# daplink_pzh.net
KiCad netlist of a schematic drawn in Altium Designer
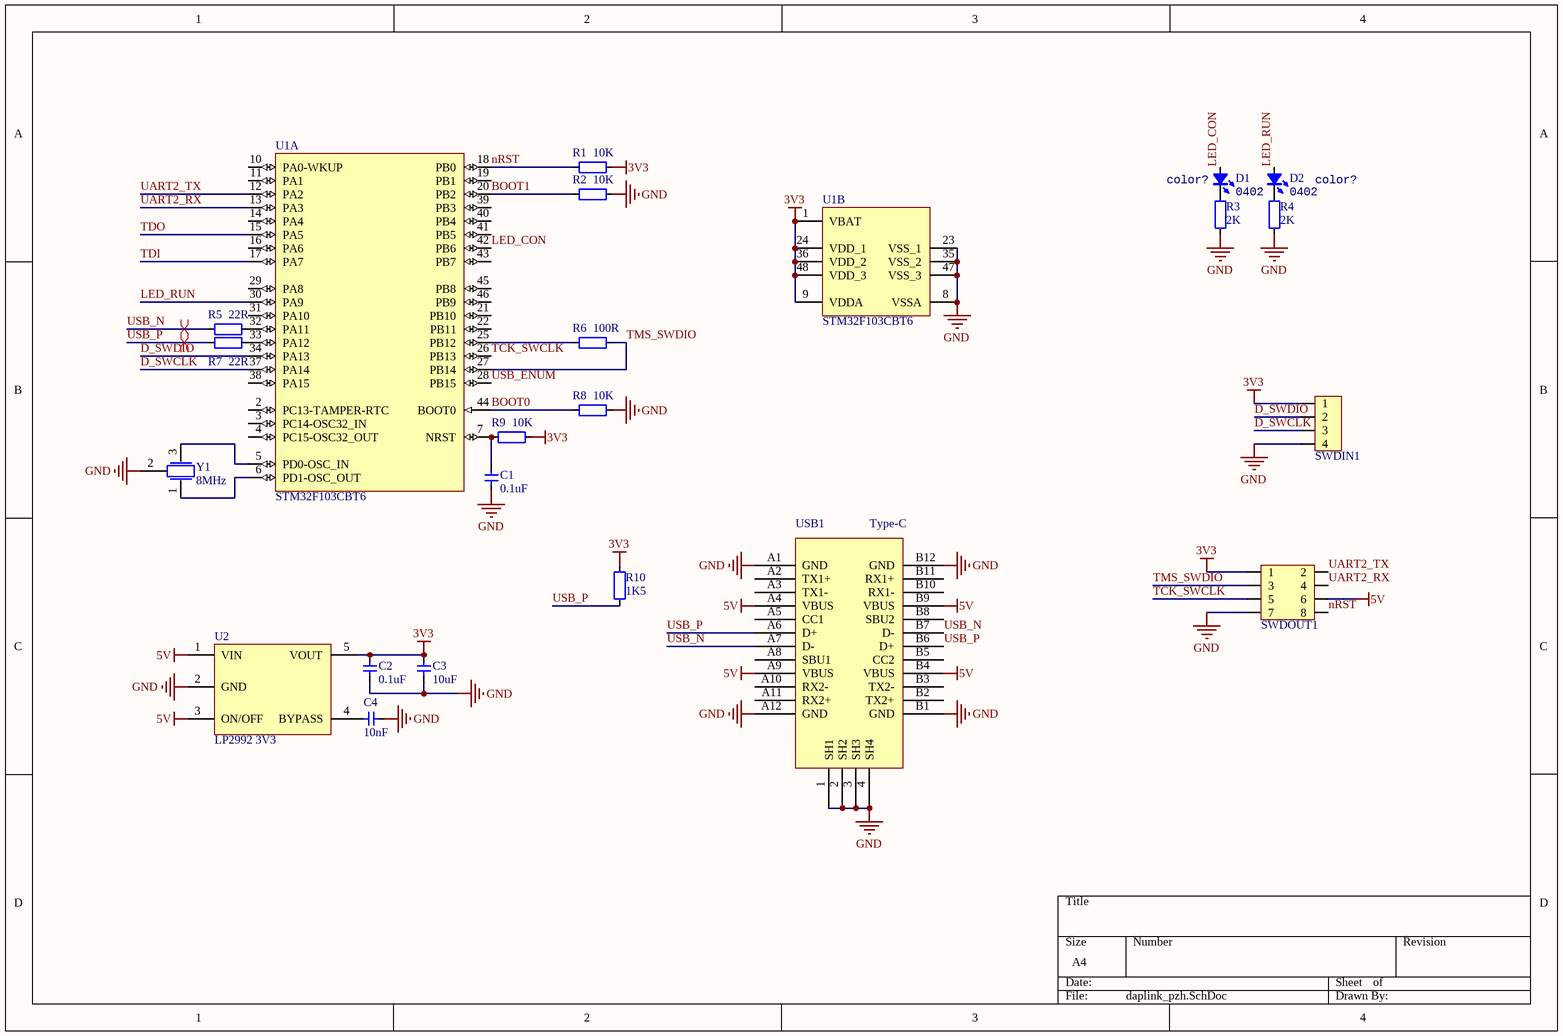
[diagram p0: daplink_pzh.SchDoc]

(export (version "E")
  (design (tool "Eeschema 10.0.6"))
  (components
    (comp (ref "C1")
      (value "0.1uF")
      (footprint "CAP_0402")
      (description "Capacitor")
      (libsource (lib "MyPcbLib") (part "电容-0402"))
    )
    (comp (ref "C2")
      (value "0.1uF")
      (footprint "CAP_0402")
      (description "Capacitor")
      (libsource (lib "MyPcbLib") (part "电容-0402"))
    )
    (comp (ref "C3")
      (value "10uF")
      (footprint "CAP_0402")
      (description "Capacitor")
      (libsource (lib "MyPcbLib") (part "电容-0402"))
    )
    (comp (ref "C4")
      (value "10nF")
      (footprint "CAP_0402")
      (description "Capacitor")
      (libsource (lib "MyPcbLib") (part "电容-0402"))
    )
    (comp (ref "D1")
      (value "color?")
      (footprint "LED_0402_RED")
      (description "LED")
      (fields (field (name "TYPE") "0402"))
      (libsource (lib "KitSprout") (part "LED_0402"))
    )
    (comp (ref "D2")
      (value "color?")
      (footprint "LED_0402_RED")
      (description "LED")
      (fields (field (name "TYPE") "0402"))
      (libsource (lib "KitSprout") (part "LED_0402"))
    )
    (comp (ref "R1")
      (value "10K")
      (footprint "RES_0402")
      (description "Resistor")
      (libsource (lib "MyPcbLib") (part "电阻-0402"))
    )
    (comp (ref "R2")
      (value "10K")
      (footprint "RES_0402")
      (description "Resistor")
      (libsource (lib "MyPcbLib") (part "电阻-0402"))
    )
    (comp (ref "R3")
      (value "2K")
      (footprint "RES_0402")
      (description "Resistor")
      (libsource (lib "") (part "电阻-0402_1"))
    )
    (comp (ref "R4")
      (value "2K")
      (footprint "RES_0402")
      (description "Resistor")
      (libsource (lib "") (part "电阻-0402_1"))
    )
    (comp (ref "R5")
      (value "22R")
      (footprint "RES_0402")
      (description "Resistor")
      (libsource (lib "MyPcbLib") (part "电阻-0402"))
    )
    (comp (ref "R6")
      (value "100R")
      (footprint "RES_0402")
      (description "Resistor")
      (libsource (lib "MyPcbLib") (part "电阻-0402"))
    )
    (comp (ref "R7")
      (value "22R")
      (footprint "RES_0402")
      (description "Resistor")
      (libsource (lib "MyPcbLib") (part "电阻-0402"))
    )
    (comp (ref "R8")
      (value "10K")
      (footprint "RES_0402")
      (description "Resistor")
      (libsource (lib "MyPcbLib") (part "电阻-0402"))
    )
    (comp (ref "R9")
      (value "10K")
      (footprint "RES_0402")
      (description "Resistor")
      (libsource (lib "MyPcbLib") (part "电阻-0402"))
    )
    (comp (ref "R10")
      (value "1K5")
      (footprint "RES_0402")
      (description "Resistor")
      (libsource (lib "") (part "电阻-0402_1"))
    )
    (comp (ref "SWDIN1")
      (value "HDR1x4hole_1.25")
      (footprint "HDR1X4_1.27_180")
      (description "Header")
      (libsource (lib "MyPcbLib") (part "HDR1x4hole_1.25"))
    )
    (comp (ref "SWDOUT1")
      (value "HDR2x4_2.54")
      (footprint "HDR2X4_2.54_180H")
      (description "Header")
      (libsource (lib "MyPcbLib") (part "HDR2x4_2.54"))
    )
    (comp (ref "U1")
      (value "STM32F103CBT6")
      (footprint "LQFP-48")
      (libsource (lib "STMicroelectronics STM32 F1") (part "STM32F103CBT6"))
    )
    (comp (ref "U2")
      (value "LP2992 3V3")
      (footprint "SOT23-5")
      (description "LDO")
      (libsource (lib "MyPcbLib") (part "LP2992"))
    )
    (comp (ref "USB1")
      (value "Type-C")
      (footprint "Type-C-TOP")
      (libsource (lib "MyPcbLib") (part "USB-Type-C-TOP"))
    )
    (comp (ref "Y1")
      (value "8MHz")
      (footprint "晶振-3P")
      (description "村田贴片")
      (libsource (lib "MyPcbLib") (part "晶振-3Pin"))
    )
  )
  (nets
    (net (code "1") (name "/BOOT0") (class "Default")
      (node (ref "R8") (pin "1") (pinfunction "1_1") (pintype "passive"))
      (node (ref "U1") (pin "44") (pinfunction "BOOT0_44") (pintype "input"))
    )
    (net (code "2") (name "/BOOT1") (class "Default")
      (node (ref "R2") (pin "1") (pinfunction "1_1") (pintype "passive"))
      (node (ref "U1") (pin "20") (pinfunction "PB2_20") (pintype "bidirectional"))
    )
    (net (code "3") (name "/D_SWCLK") (class "Default")
      (node (ref "SWDIN1") (pin "3") (pinfunction "3_3") (pintype "passive"))
      (node (ref "U1") (pin "37") (pinfunction "PA14_37") (pintype "bidirectional"))
    )
    (net (code "4") (name "/D_SWDIO") (class "Default")
      (node (ref "SWDIN1") (pin "2") (pinfunction "2_2") (pintype "passive"))
      (node (ref "U1") (pin "34") (pinfunction "PA13_34") (pintype "bidirectional"))
    )
    (net (code "5") (name "/LED_CON") (class "Default")
      (node (ref "D1") (pin "1") (pinfunction "A_1") (pintype "passive"))
      (node (ref "U1") (pin "42") (pinfunction "PB6_42") (pintype "bidirectional"))
    )
    (net (code "6") (name "/LED_RUN") (class "Default")
      (node (ref "D2") (pin "1") (pinfunction "A_1") (pintype "passive"))
      (node (ref "U1") (pin "30") (pinfunction "PA9_30") (pintype "bidirectional"))
    )
    (net (code "7") (name "/TCK_SWCLK") (class "Default")
      (node (ref "SWDOUT1") (pin "5") (pinfunction "5_5") (pintype "passive"))
      (node (ref "U1") (pin "26") (pinfunction "PB13_26") (pintype "bidirectional"))
    )
    (net (code "8") (name "/TDI") (class "Default")
      (node (ref "U1") (pin "17") (pinfunction "PA7_17") (pintype "bidirectional"))
    )
    (net (code "9") (name "/TDO") (class "Default")
      (node (ref "U1") (pin "15") (pinfunction "PA5_15") (pintype "bidirectional"))
    )
    (net (code "10") (name "/TMS_SWDIO") (class "Default")
      (node (ref "R6") (pin "2") (pinfunction "2_2") (pintype "passive"))
      (node (ref "SWDOUT1") (pin "3") (pinfunction "3_3") (pintype "passive"))
      (node (ref "U1") (pin "27") (pinfunction "PB14_27") (pintype "bidirectional"))
    )
    (net (code "11") (name "/UART2_RX") (class "Default")
      (node (ref "SWDOUT1") (pin "4") (pinfunction "4_4") (pintype "passive"))
      (node (ref "U1") (pin "13") (pinfunction "PA3_13") (pintype "bidirectional"))
    )
    (net (code "12") (name "/UART2_TX") (class "Default")
      (node (ref "SWDOUT1") (pin "2") (pinfunction "2_2") (pintype "passive"))
      (node (ref "U1") (pin "12") (pinfunction "PA2_12") (pintype "bidirectional"))
    )
    (net (code "13") (name "/USB_ENUM") (class "Default")
      (node (ref "U1") (pin "28") (pinfunction "PB15_28") (pintype "bidirectional"))
    )
    (net (code "14") (name "/USB_N") (class "Default")
      (node (ref "R5") (pin "1") (pinfunction "1_1") (pintype "passive"))
      (node (ref "USB1") (pin "A7") (pinfunction "D-_A7") (pintype "passive"))
      (node (ref "USB1") (pin "B7") (pinfunction "D-_B7") (pintype "passive"))
    )
    (net (code "15") (name "/USB_P") (class "Default")
      (node (ref "R10") (pin "1") (pinfunction "1_1") (pintype "passive"))
      (node (ref "R7") (pin "1") (pinfunction "1_1") (pintype "passive"))
      (node (ref "USB1") (pin "A6") (pinfunction "D+_A6") (pintype "passive"))
      (node (ref "USB1") (pin "B6") (pinfunction "D+_B6") (pintype "passive"))
    )
    (net (code "16") (name "/nRST") (class "Default")
      (node (ref "R1") (pin "1") (pinfunction "1_1") (pintype "passive"))
      (node (ref "SWDOUT1") (pin "8") (pinfunction "8_8") (pintype "passive"))
      (node (ref "U1") (pin "18") (pinfunction "PB0_18") (pintype "bidirectional"))
    )
    (net (code "17") (name "3V3") (class "Default")
      (node (ref "C2") (pin "2") (pinfunction "2_2") (pintype "passive"))
      (node (ref "C3") (pin "2") (pinfunction "2_2") (pintype "passive"))
      (node (ref "R1") (pin "2") (pinfunction "2_2") (pintype "passive"))
      (node (ref "R10") (pin "2") (pinfunction "2_2") (pintype "passive"))
      (node (ref "R9") (pin "2") (pinfunction "2_2") (pintype "passive"))
      (node (ref "SWDIN1") (pin "1") (pinfunction "1_1") (pintype "passive"))
      (node (ref "SWDOUT1") (pin "1") (pinfunction "1_1") (pintype "passive"))
      (node (ref "U1") (pin "1") (pinfunction "VBAT_1") (pintype "power_in"))
      (node (ref "U1") (pin "24") (pinfunction "VDD_1_24") (pintype "power_in"))
      (node (ref "U1") (pin "36") (pinfunction "VDD_2_36") (pintype "power_in"))
      (node (ref "U1") (pin "48") (pinfunction "VDD_3_48") (pintype "power_in"))
      (node (ref "U1") (pin "9") (pinfunction "VDDA_9") (pintype "power_in"))
      (node (ref "U2") (pin "5") (pinfunction "VOUT_5") (pintype "passive"))
    )
    (net (code "18") (name "5V") (class "Default")
      (node (ref "SWDOUT1") (pin "6") (pinfunction "6_6") (pintype "passive"))
      (node (ref "U2") (pin "1") (pinfunction "VIN_1") (pintype "passive"))
      (node (ref "U2") (pin "3") (pinfunction "ON/OFF_3") (pintype "passive"))
      (node (ref "USB1") (pin "A4") (pinfunction "VBUS_A4") (pintype "passive"))
      (node (ref "USB1") (pin "A9") (pinfunction "VBUS_A9") (pintype "passive"))
      (node (ref "USB1") (pin "B4") (pinfunction "VBUS_B4") (pintype "passive"))
      (node (ref "USB1") (pin "B9") (pinfunction "VBUS_B9") (pintype "passive"))
    )
    (net (code "19") (name "GND") (class "Default")
      (node (ref "C1") (pin "1") (pinfunction "1_1") (pintype "passive"))
      (node (ref "C2") (pin "1") (pinfunction "1_1") (pintype "passive"))
      (node (ref "C3") (pin "1") (pinfunction "1_1") (pintype "passive"))
      (node (ref "C4") (pin "1") (pinfunction "1_1") (pintype "passive"))
      (node (ref "R2") (pin "2") (pinfunction "2_2") (pintype "passive"))
      (node (ref "R3") (pin "1") (pinfunction "1_1") (pintype "passive"))
      (node (ref "R4") (pin "1") (pinfunction "1_1") (pintype "passive"))
      (node (ref "R8") (pin "2") (pinfunction "2_2") (pintype "passive"))
      (node (ref "SWDIN1") (pin "4") (pinfunction "4_4") (pintype "passive"))
      (node (ref "SWDOUT1") (pin "7") (pinfunction "7_7") (pintype "passive"))
      (node (ref "U1") (pin "23") (pinfunction "VSS_1_23") (pintype "power_in"))
      (node (ref "U1") (pin "35") (pinfunction "VSS_2_35") (pintype "power_in"))
      (node (ref "U1") (pin "47") (pinfunction "VSS_3_47") (pintype "power_in"))
      (node (ref "U1") (pin "8") (pinfunction "VSSA_8") (pintype "power_in"))
      (node (ref "U2") (pin "2") (pinfunction "GND_2") (pintype "passive"))
      (node (ref "USB1") (pin "1") (pinfunction "SH1_1") (pintype "passive"))
      (node (ref "USB1") (pin "2") (pinfunction "SH2_2") (pintype "passive"))
      (node (ref "USB1") (pin "3") (pinfunction "SH3_3") (pintype "passive"))
      (node (ref "USB1") (pin "4") (pinfunction "SH4_4") (pintype "passive"))
      (node (ref "USB1") (pin "A1") (pinfunction "GND_A1") (pintype "passive"))
      (node (ref "USB1") (pin "A12") (pinfunction "GND_A12") (pintype "passive"))
      (node (ref "USB1") (pin "B1") (pinfunction "GND_B1") (pintype "passive"))
      (node (ref "USB1") (pin "B12") (pinfunction "GND_B12") (pintype "passive"))
      (node (ref "Y1") (pin "2") (pinfunction "2_2") (pintype "passive"))
    )
    (net (code "20") (name "Net-(D1-K)") (class "Default")
      (node (ref "D1") (pin "2") (pinfunction "K_2") (pintype "passive"))
      (node (ref "R3") (pin "2") (pinfunction "2_2") (pintype "passive"))
    )
    (net (code "21") (name "Net-(D2-K)") (class "Default")
      (node (ref "D2") (pin "2") (pinfunction "K_2") (pintype "passive"))
      (node (ref "R4") (pin "2") (pinfunction "2_2") (pintype "passive"))
    )
    (net (code "22") (name "Net-(U1A-NRST)") (class "Default")
      (node (ref "C1") (pin "2") (pinfunction "2_2") (pintype "passive"))
      (node (ref "R9") (pin "1") (pinfunction "1_1") (pintype "passive"))
      (node (ref "U1") (pin "7") (pinfunction "NRST_7") (pintype "bidirectional"))
    )
    (net (code "23") (name "Net-(U1A-PA11)") (class "Default")
      (node (ref "R5") (pin "2") (pinfunction "2_2") (pintype "passive"))
      (node (ref "U1") (pin "32") (pinfunction "PA11_32") (pintype "bidirectional"))
    )
    (net (code "24") (name "Net-(U1A-PA12)") (class "Default")
      (node (ref "R7") (pin "2") (pinfunction "2_2") (pintype "passive"))
      (node (ref "U1") (pin "33") (pinfunction "PA12_33") (pintype "bidirectional"))
    )
    (net (code "25") (name "Net-(U1A-PB12)") (class "Default")
      (node (ref "R6") (pin "1") (pinfunction "1_1") (pintype "passive"))
      (node (ref "U1") (pin "25") (pinfunction "PB12_25") (pintype "bidirectional"))
    )
    (net (code "26") (name "Net-(U1A-PD0-OSC_IN)") (class "Default")
      (node (ref "U1") (pin "5") (pinfunction "PD0-OSC_IN_5") (pintype "bidirectional"))
      (node (ref "Y1") (pin "3") (pinfunction "3_3") (pintype "passive"))
    )
    (net (code "27") (name "Net-(U1A-PD1-OSC_OUT)") (class "Default")
      (node (ref "U1") (pin "6") (pinfunction "PD1-OSC_OUT_6") (pintype "bidirectional"))
      (node (ref "Y1") (pin "1") (pinfunction "1_1") (pintype "passive"))
    )
    (net (code "28") (name "Net-(U2-BYPASS)") (class "Default")
      (node (ref "C4") (pin "2") (pinfunction "2_2") (pintype "passive"))
      (node (ref "U2") (pin "4") (pinfunction "BYPASS_4") (pintype "passive"))
    )
    (net (code "29") (name "unconnected-(U1A-PA0-WKUP-Pad10)") (class "Default")
      (node (ref "U1") (pin "10") (pinfunction "PA0-WKUP_10") (pintype "bidirectional"))
    )
    (net (code "30") (name "unconnected-(U1A-PA1-Pad11)") (class "Default")
      (node (ref "U1") (pin "11") (pinfunction "PA1_11") (pintype "bidirectional"))
    )
    (net (code "31") (name "unconnected-(U1A-PA4-Pad14)") (class "Default")
      (node (ref "U1") (pin "14") (pinfunction "PA4_14") (pintype "bidirectional"))
    )
    (net (code "32") (name "unconnected-(U1A-PA6-Pad16)") (class "Default")
      (node (ref "U1") (pin "16") (pinfunction "PA6_16") (pintype "bidirectional"))
    )
    (net (code "33") (name "unconnected-(U1A-PA8-Pad29)") (class "Default")
      (node (ref "U1") (pin "29") (pinfunction "PA8_29") (pintype "bidirectional"))
    )
    (net (code "34") (name "unconnected-(U1A-PA10-Pad31)") (class "Default")
      (node (ref "U1") (pin "31") (pinfunction "PA10_31") (pintype "bidirectional"))
    )
    (net (code "35") (name "unconnected-(U1A-PA15-Pad38)") (class "Default")
      (node (ref "U1") (pin "38") (pinfunction "PA15_38") (pintype "bidirectional"))
    )
    (net (code "36") (name "unconnected-(U1A-PB1-Pad19)") (class "Default")
      (node (ref "U1") (pin "19") (pinfunction "PB1_19") (pintype "bidirectional"))
    )
    (net (code "37") (name "unconnected-(U1A-PB3-Pad39)") (class "Default")
      (node (ref "U1") (pin "39") (pinfunction "PB3_39") (pintype "bidirectional"))
    )
    (net (code "38") (name "unconnected-(U1A-PB4-Pad40)") (class "Default")
      (node (ref "U1") (pin "40") (pinfunction "PB4_40") (pintype "bidirectional"))
    )
    (net (code "39") (name "unconnected-(U1A-PB5-Pad41)") (class "Default")
      (node (ref "U1") (pin "41") (pinfunction "PB5_41") (pintype "bidirectional"))
    )
    (net (code "40") (name "unconnected-(U1A-PB7-Pad43)") (class "Default")
      (node (ref "U1") (pin "43") (pinfunction "PB7_43") (pintype "bidirectional"))
    )
    (net (code "41") (name "unconnected-(U1A-PB8-Pad45)") (class "Default")
      (node (ref "U1") (pin "45") (pinfunction "PB8_45") (pintype "bidirectional"))
    )
    (net (code "42") (name "unconnected-(U1A-PB9-Pad46)") (class "Default")
      (node (ref "U1") (pin "46") (pinfunction "PB9_46") (pintype "bidirectional"))
    )
    (net (code "43") (name "unconnected-(U1A-PB10-Pad21)") (class "Default")
      (node (ref "U1") (pin "21") (pinfunction "PB10_21") (pintype "bidirectional"))
    )
    (net (code "44") (name "unconnected-(U1A-PB11-Pad22)") (class "Default")
      (node (ref "U1") (pin "22") (pinfunction "PB11_22") (pintype "bidirectional"))
    )
    (net (code "45") (name "unconnected-(U1A-PC13-TAMPER-RTC-Pad2)") (class "Default")
      (node (ref "U1") (pin "2") (pinfunction "PC13-TAMPER-RTC_2") (pintype "bidirectional"))
    )
    (net (code "46") (name "unconnected-(U1A-PC14-OSC32_IN-Pad3)") (class "Default")
      (node (ref "U1") (pin "3") (pinfunction "PC14-OSC32_IN_3") (pintype "bidirectional"))
    )
    (net (code "47") (name "unconnected-(U1A-PC15-OSC32_OUT-Pad4)") (class "Default")
      (node (ref "U1") (pin "4") (pinfunction "PC15-OSC32_OUT_4") (pintype "bidirectional"))
    )
    (net (code "48") (name "unconnected-(USB1-CC1-PadA5)") (class "Default")
      (node (ref "USB1") (pin "A5") (pinfunction "CC1_A5") (pintype "passive"))
    )
    (net (code "49") (name "unconnected-(USB1-CC2-PadB5)") (class "Default")
      (node (ref "USB1") (pin "B5") (pinfunction "CC2_B5") (pintype "passive"))
    )
    (net (code "50") (name "unconnected-(USB1-RX1+-PadB11)") (class "Default")
      (node (ref "USB1") (pin "B11") (pinfunction "RX1+_B11") (pintype "passive"))
    )
    (net (code "51") (name "unconnected-(USB1-RX1--PadB10)") (class "Default")
      (node (ref "USB1") (pin "B10") (pinfunction "RX1-_B10") (pintype "passive"))
    )
    (net (code "52") (name "unconnected-(USB1-RX2+-PadA11)") (class "Default")
      (node (ref "USB1") (pin "A11") (pinfunction "RX2+_A11") (pintype "passive"))
    )
    (net (code "53") (name "unconnected-(USB1-RX2--PadA10)") (class "Default")
      (node (ref "USB1") (pin "A10") (pinfunction "RX2-_A10") (pintype "passive"))
    )
    (net (code "54") (name "unconnected-(USB1-SBU1-PadA8)") (class "Default")
      (node (ref "USB1") (pin "A8") (pinfunction "SBU1_A8") (pintype "passive"))
    )
    (net (code "55") (name "unconnected-(USB1-SBU2-PadB8)") (class "Default")
      (node (ref "USB1") (pin "B8") (pinfunction "SBU2_B8") (pintype "passive"))
    )
    (net (code "56") (name "unconnected-(USB1-TX1+-PadA2)") (class "Default")
      (node (ref "USB1") (pin "A2") (pinfunction "TX1+_A2") (pintype "passive"))
    )
    (net (code "57") (name "unconnected-(USB1-TX1--PadA3)") (class "Default")
      (node (ref "USB1") (pin "A3") (pinfunction "TX1-_A3") (pintype "passive"))
    )
    (net (code "58") (name "unconnected-(USB1-TX2+-PadB2)") (class "Default")
      (node (ref "USB1") (pin "B2") (pinfunction "TX2+_B2") (pintype "passive"))
    )
    (net (code "59") (name "unconnected-(USB1-TX2--PadB3)") (class "Default")
      (node (ref "USB1") (pin "B3") (pinfunction "TX2-_B3") (pintype "passive"))
    )
  )
)
